# iot_arduino_kap8_wemos_analog_shield.net
KiCad netlist of a schematic drawn in EAGLE
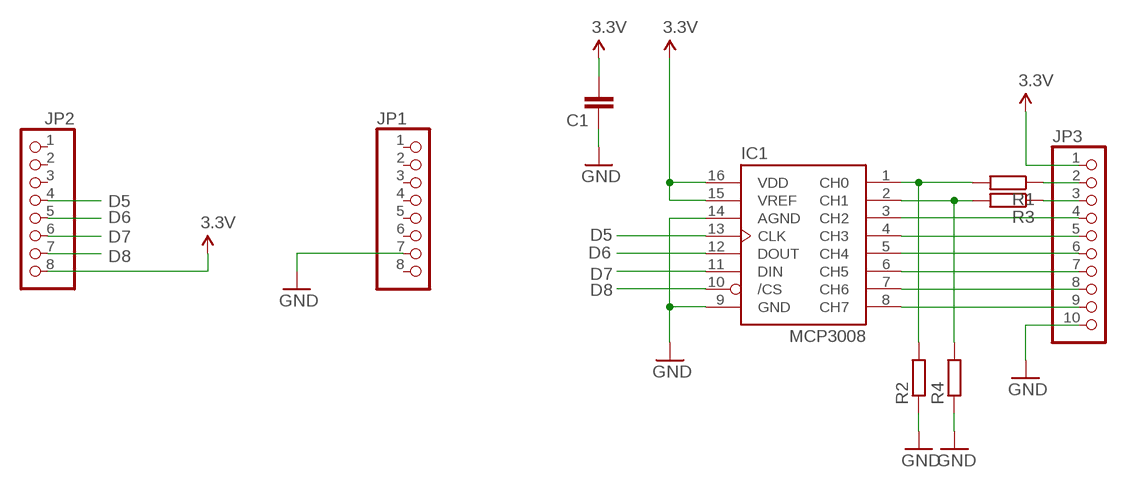
[diagram p0: schematic, sheet 1]

(export (version "E")
  (design (tool "Eeschema 10.0.6"))
  (components
    (comp (ref "C1")
      (value "C-EUC0805K")
      (footprint "eagle-import:C0805K")
      (libsource (lib "eagle-import") (part "C-EUC0805K"))
    )
    (comp (ref "IC1")
      (value "MCP3008")
      (footprint "eagle-import:DIL16")
      (libsource (lib "eagle-import") (part "MCP3008"))
    )
    (comp (ref "JP1")
      (value "PINHD-1X8")
      (footprint "eagle-import:1X08")
      (libsource (lib "eagle-import") (part "PINHD-1X8"))
    )
    (comp (ref "JP2")
      (value "PINHD-1X8")
      (footprint "eagle-import:1X08")
      (libsource (lib "eagle-import") (part "PINHD-1X8"))
    )
    (comp (ref "JP3")
      (value "PINHD-1X10")
      (footprint "eagle-import:1X10")
      (libsource (lib "eagle-import") (part "PINHD-1X10"))
    )
    (comp (ref "R1")
      (value "R-EU_M0805")
      (footprint "eagle-import:M0805")
      (libsource (lib "eagle-import") (part "R-EU_M0805"))
    )
    (comp (ref "R2")
      (value "R-EU_M0805")
      (footprint "eagle-import:M0805")
      (libsource (lib "eagle-import") (part "R-EU_M0805"))
    )
    (comp (ref "R3")
      (value "R-EU_M0805")
      (footprint "eagle-import:M0805")
      (libsource (lib "eagle-import") (part "R-EU_M0805"))
    )
    (comp (ref "R4")
      (value "R-EU_M0805")
      (footprint "eagle-import:M0805")
      (libsource (lib "eagle-import") (part "R-EU_M0805"))
    )
  )
  (nets
    (net (code "1") (name "/D5") (class "Default")
      (node (ref "IC1") (pin "13") (pinfunction "CLK_13") (pintype "input"))
      (node (ref "JP2") (pin "4") (pinfunction "4_4") (pintype "passive"))
    )
    (net (code "2") (name "/D6") (class "Default")
      (node (ref "IC1") (pin "12") (pinfunction "DOUT_12") (pintype "output"))
      (node (ref "JP2") (pin "5") (pinfunction "5_5") (pintype "passive"))
    )
    (net (code "3") (name "/D7") (class "Default")
      (node (ref "IC1") (pin "11") (pinfunction "DIN_11") (pintype "input"))
      (node (ref "JP2") (pin "6") (pinfunction "6_6") (pintype "passive"))
    )
    (net (code "4") (name "/D8") (class "Default")
      (node (ref "IC1") (pin "10") (pinfunction "/CS_10") (pintype "input"))
      (node (ref "JP2") (pin "7") (pinfunction "7_7") (pintype "passive"))
    )
    (net (code "5") (name "3.3V") (class "Default")
      (node (ref "C1") (pin "2") (pinfunction "2_2") (pintype "passive"))
      (node (ref "IC1") (pin "15") (pinfunction "VREF_15") (pintype "input"))
      (node (ref "IC1") (pin "16") (pinfunction "VDD_16") (pintype "power_in"))
      (node (ref "JP2") (pin "8") (pinfunction "8_8") (pintype "passive"))
      (node (ref "JP3") (pin "1") (pinfunction "1_1") (pintype "passive"))
    )
    (net (code "6") (name "GND") (class "Default")
      (node (ref "C1") (pin "1") (pinfunction "1_1") (pintype "passive"))
      (node (ref "IC1") (pin "14") (pinfunction "AGND_14") (pintype "power_in"))
      (node (ref "IC1") (pin "9") (pinfunction "GND_9") (pintype "power_in"))
      (node (ref "JP1") (pin "7") (pinfunction "7_7") (pintype "passive"))
      (node (ref "JP3") (pin "10") (pinfunction "10_10") (pintype "passive"))
      (node (ref "R2") (pin "1") (pinfunction "1_1") (pintype "passive"))
      (node (ref "R4") (pin "1") (pinfunction "1_1") (pintype "passive"))
    )
    (net (code "7") (name "Net-(IC1-CH0)") (class "Default")
      (node (ref "IC1") (pin "1") (pinfunction "CH0_1") (pintype "input"))
      (node (ref "R1") (pin "2") (pinfunction "2_2") (pintype "passive"))
      (node (ref "R2") (pin "2") (pinfunction "2_2") (pintype "passive"))
    )
    (net (code "8") (name "Net-(IC1-CH1)") (class "Default")
      (node (ref "IC1") (pin "2") (pinfunction "CH1_2") (pintype "input"))
      (node (ref "R3") (pin "2") (pinfunction "2_2") (pintype "passive"))
      (node (ref "R4") (pin "2") (pinfunction "2_2") (pintype "passive"))
    )
    (net (code "9") (name "Net-(IC1-CH2)") (class "Default")
      (node (ref "IC1") (pin "3") (pinfunction "CH2_3") (pintype "input"))
      (node (ref "JP3") (pin "4") (pinfunction "4_4") (pintype "passive"))
    )
    (net (code "10") (name "Net-(IC1-CH3)") (class "Default")
      (node (ref "IC1") (pin "4") (pinfunction "CH3_4") (pintype "input"))
      (node (ref "JP3") (pin "5") (pinfunction "5_5") (pintype "passive"))
    )
    (net (code "11") (name "Net-(IC1-CH4)") (class "Default")
      (node (ref "IC1") (pin "5") (pinfunction "CH4_5") (pintype "input"))
      (node (ref "JP3") (pin "6") (pinfunction "6_6") (pintype "passive"))
    )
    (net (code "12") (name "Net-(IC1-CH5)") (class "Default")
      (node (ref "IC1") (pin "6") (pinfunction "CH5_6") (pintype "input"))
      (node (ref "JP3") (pin "7") (pinfunction "7_7") (pintype "passive"))
    )
    (net (code "13") (name "Net-(IC1-CH6)") (class "Default")
      (node (ref "IC1") (pin "7") (pinfunction "CH6_7") (pintype "input"))
      (node (ref "JP3") (pin "8") (pinfunction "8_8") (pintype "passive"))
    )
    (net (code "14") (name "Net-(IC1-CH7)") (class "Default")
      (node (ref "IC1") (pin "8") (pinfunction "CH7_8") (pintype "input"))
      (node (ref "JP3") (pin "9") (pinfunction "9_9") (pintype "passive"))
    )
    (net (code "15") (name "Net-(JP3-Pad2)") (class "Default")
      (node (ref "JP3") (pin "2") (pinfunction "2_2") (pintype "passive"))
      (node (ref "R1") (pin "1") (pinfunction "1_1") (pintype "passive"))
    )
    (net (code "16") (name "Net-(JP3-Pad3)") (class "Default")
      (node (ref "JP3") (pin "3") (pinfunction "3_3") (pintype "passive"))
      (node (ref "R3") (pin "1") (pinfunction "1_1") (pintype "passive"))
    )
    (net (code "17") (name "unconnected-(JP1-Pad1)") (class "Default")
      (node (ref "JP1") (pin "1") (pinfunction "1_1") (pintype "passive"))
    )
    (net (code "18") (name "unconnected-(JP1-Pad2)") (class "Default")
      (node (ref "JP1") (pin "2") (pinfunction "2_2") (pintype "passive"))
    )
    (net (code "19") (name "unconnected-(JP1-Pad3)") (class "Default")
      (node (ref "JP1") (pin "3") (pinfunction "3_3") (pintype "passive"))
    )
    (net (code "20") (name "unconnected-(JP1-Pad4)") (class "Default")
      (node (ref "JP1") (pin "4") (pinfunction "4_4") (pintype "passive"))
    )
    (net (code "21") (name "unconnected-(JP1-Pad5)") (class "Default")
      (node (ref "JP1") (pin "5") (pinfunction "5_5") (pintype "passive"))
    )
    (net (code "22") (name "unconnected-(JP1-Pad6)") (class "Default")
      (node (ref "JP1") (pin "6") (pinfunction "6_6") (pintype "passive"))
    )
    (net (code "23") (name "unconnected-(JP1-Pad8)") (class "Default")
      (node (ref "JP1") (pin "8") (pinfunction "8_8") (pintype "passive"))
    )
    (net (code "24") (name "unconnected-(JP2-Pad1)") (class "Default")
      (node (ref "JP2") (pin "1") (pinfunction "1_1") (pintype "passive"))
    )
    (net (code "25") (name "unconnected-(JP2-Pad2)") (class "Default")
      (node (ref "JP2") (pin "2") (pinfunction "2_2") (pintype "passive"))
    )
    (net (code "26") (name "unconnected-(JP2-Pad3)") (class "Default")
      (node (ref "JP2") (pin "3") (pinfunction "3_3") (pintype "passive"))
    )
  )
)
